# Final_Power_Supply_Design_PCB.net
KiCad netlist of a schematic drawn in EAGLE
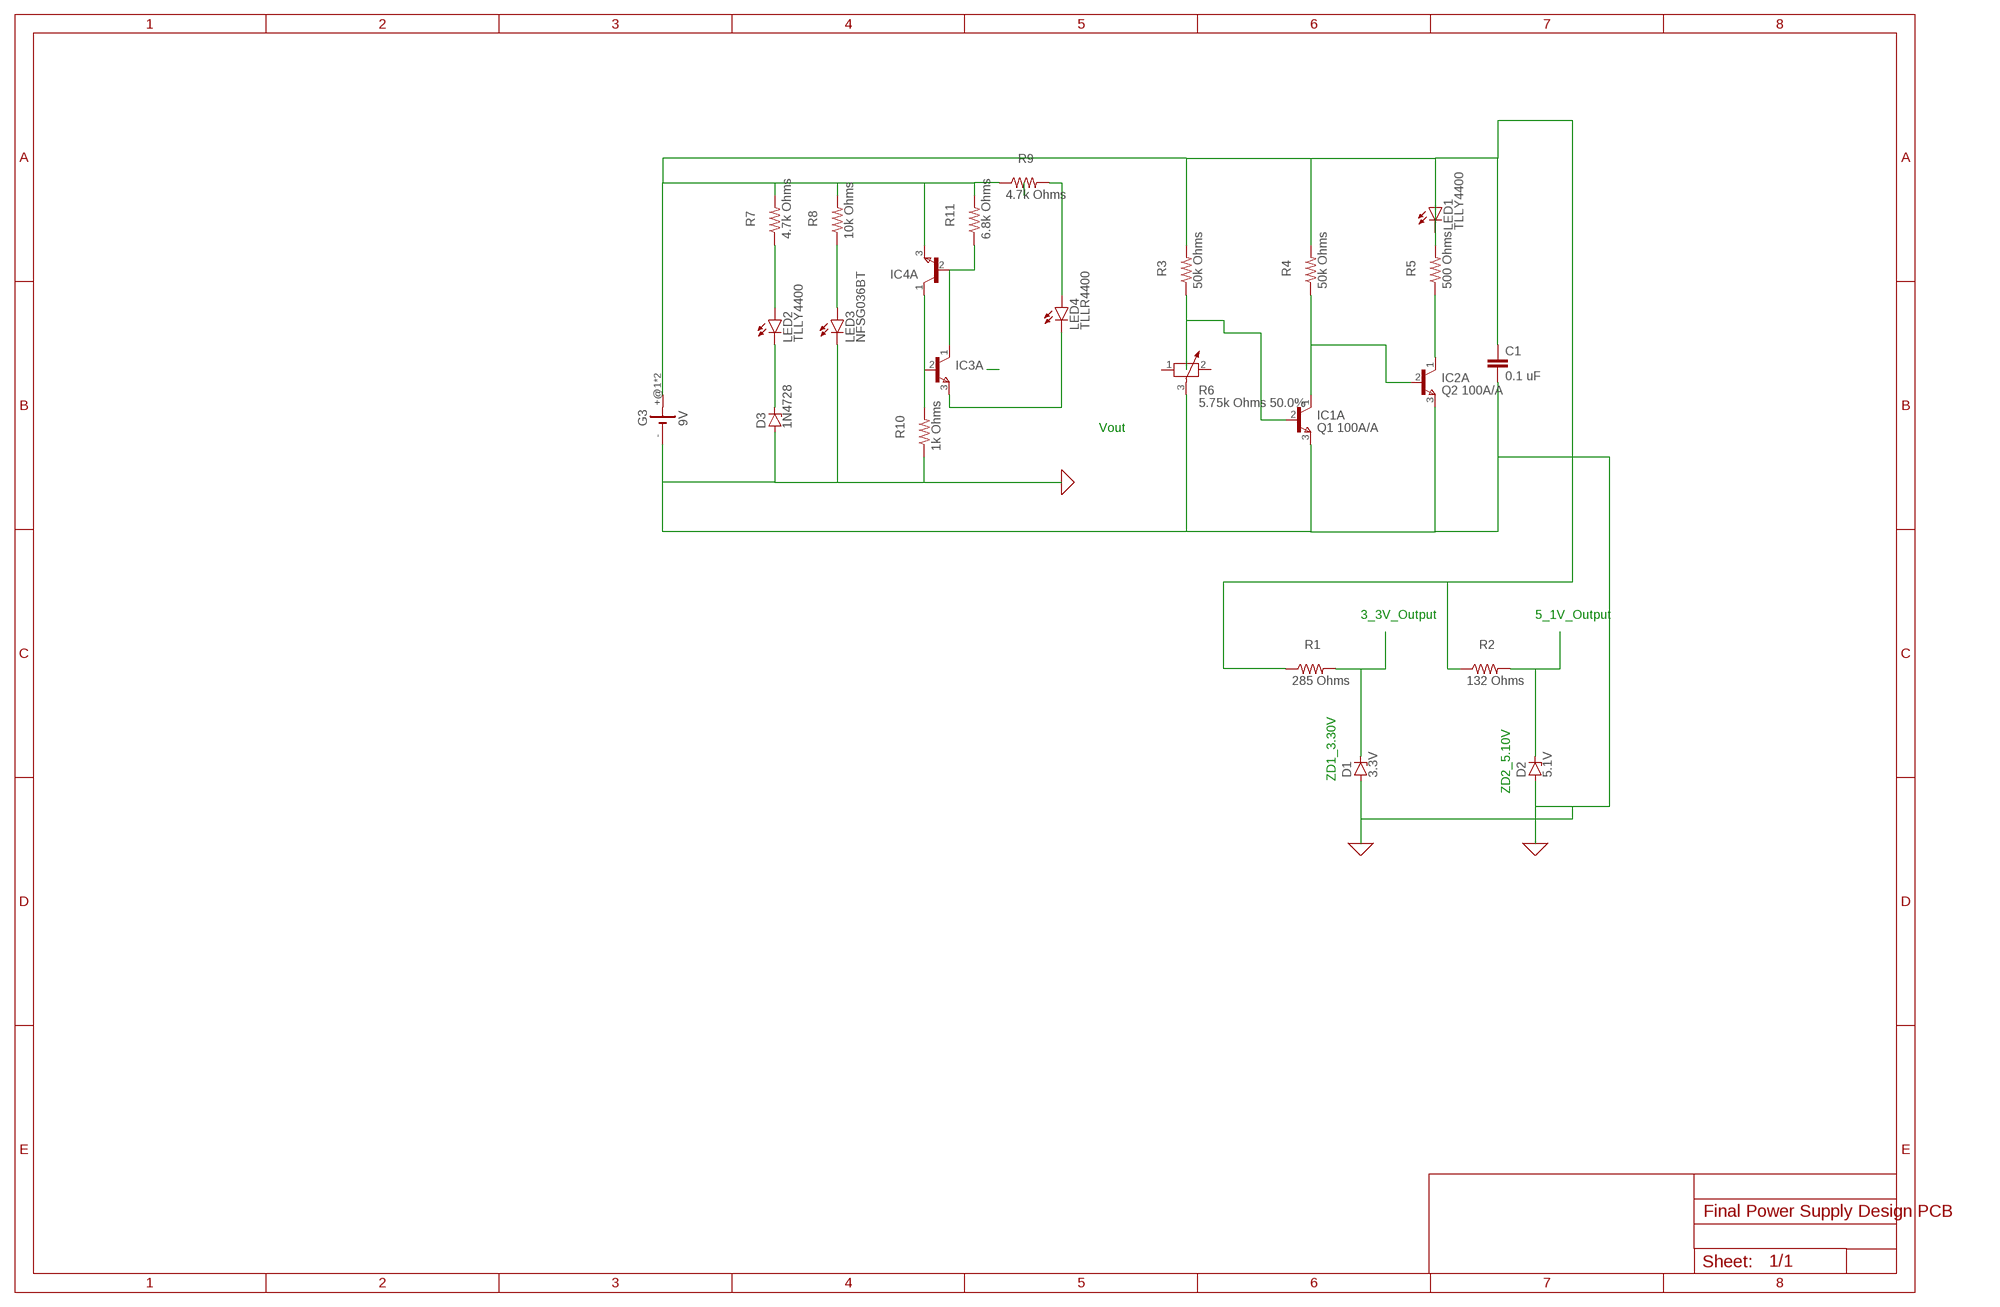
[diagram p0: schematic, sheet 1]

(export (version "E")
  (design (tool "Eeschema 10.0.6"))
  (components
    (comp (ref "C1")
      (value "0.1 uF")
      (footprint "eagle-import:C2.5-4")
      (libsource (lib "eagle-import") (part "C2.5/4"))
    )
    (comp (ref "D1")
      (value "3.3V")
      (footprint "eagle-import:DO41Z10")
      (libsource (lib "eagle-import") (part "1N4728"))
    )
    (comp (ref "D2")
      (value "5.1V")
      (footprint "eagle-import:DO41Z10")
      (libsource (lib "eagle-import") (part "1N4728"))
    )
    (comp (ref "D3")
      (value "1N4728")
      (footprint "eagle-import:DO41Z10")
      (libsource (lib "eagle-import") (part "1N4728"))
    )
    (comp (ref "G3")
      (value "9V")
      (footprint "eagle-import:10MM_SM_COIN_CELL_CLIP")
      (libsource (lib "eagle-import") (part "10MM_SM_COIN_CELL_CLIP"))
    )
    (comp (ref "IC1")
      (value "Q1 100A/A")
      (footprint "eagle-import:TO78")
      (libsource (lib "eagle-import") (part "MAT-01H"))
    )
    (comp (ref "IC2")
      (value "Q2 100A/A")
      (footprint "eagle-import:TO78")
      (libsource (lib "eagle-import") (part "MAT-01H"))
    )
    (comp (ref "IC3")
      (value "MAT-01H")
      (footprint "eagle-import:TO78")
      (libsource (lib "eagle-import") (part "MAT-01H"))
    )
    (comp (ref "IC4")
      (value "MAT-01H")
      (footprint "eagle-import:TO78")
      (libsource (lib "eagle-import") (part "MAT-01H"))
    )
    (comp (ref "LED1")
      (value "TLLY4400")
      (footprint "eagle-import:LED3MM")
      (fields (field (name "MF") "VISHAY SEMICONDUCTOR"))
      (libsource (lib "eagle-import") (part "TLLY4400"))
    )
    (comp (ref "LED2")
      (value "TLLY4400")
      (footprint "eagle-import:LED3MM")
      (fields (field (name "MF") "VISHAY SEMICONDUCTOR"))
      (libsource (lib "eagle-import") (part "TLLY4400"))
    )
    (comp (ref "LED3")
      (value "NFSG036BT")
      (footprint "eagle-import:NFSG036BT")
      (libsource (lib "eagle-import") (part "NFSG036BT"))
    )
    (comp (ref "LED4")
      (value "TLLR4400")
      (footprint "eagle-import:LED3MM")
      (fields (field (name "MF") "VISHAY SEMICONDUCTOR"))
      (libsource (lib "eagle-import") (part "TLLR4400"))
    )
    (comp (ref "R1")
      (value "285 Ohms")
      (footprint "eagle-import:0204V")
      (libsource (lib "eagle-import") (part "R-US_0204/2V"))
    )
    (comp (ref "R2")
      (value "132 Ohms")
      (footprint "eagle-import:0204V")
      (libsource (lib "eagle-import") (part "R-US_0204/2V"))
    )
    (comp (ref "R3")
      (value "50k Ohms")
      (footprint "eagle-import:0204V")
      (libsource (lib "eagle-import") (part "R-US_0204/2V"))
    )
    (comp (ref "R4")
      (value "50k Ohms")
      (footprint "eagle-import:0204V")
      (libsource (lib "eagle-import") (part "R-US_0204/2V"))
    )
    (comp (ref "R5")
      (value "500 Ohms")
      (footprint "eagle-import:0204V")
      (libsource (lib "eagle-import") (part "R-US_0204/2V"))
    )
    (comp (ref "R6")
      (value "5.75k Ohms 50.0%")
      (footprint "eagle-import:PT-10")
      (libsource (lib "eagle-import") (part "POTENTIOMETER_PT-10"))
    )
    (comp (ref "R7")
      (value "4.7k Ohms")
      (footprint "eagle-import:0204V")
      (libsource (lib "eagle-import") (part "R-US_0204/2V"))
    )
    (comp (ref "R8")
      (value "10k Ohms")
      (footprint "eagle-import:0204V")
      (libsource (lib "eagle-import") (part "R-US_0204/2V"))
    )
    (comp (ref "R9")
      (value "4.7k Ohms")
      (footprint "eagle-import:0204V")
      (libsource (lib "eagle-import") (part "R-US_0204/2V"))
    )
    (comp (ref "R10")
      (value "1k Ohms")
      (footprint "eagle-import:0204V")
      (libsource (lib "eagle-import") (part "R-US_0204/2V"))
    )
    (comp (ref "R11")
      (value "6.8k Ohms")
      (footprint "eagle-import:0204V")
      (libsource (lib "eagle-import") (part "R-US_0204/2V"))
    )
  )
  (nets
    (net (code "1") (name "GND") (class "Default")
      (node (ref "C1") (pin "2") (pinfunction "2_2") (pintype "passive"))
      (node (ref "D1") (pin "A") (pinfunction "A_A") (pintype "passive"))
      (node (ref "D2") (pin "A") (pinfunction "A_A") (pintype "passive"))
      (node (ref "D3") (pin "A") (pinfunction "A_A") (pintype "passive"))
      (node (ref "G3") (pin "-") (pinfunction "-_-") (pintype "passive"))
      (node (ref "IC1") (pin "3") (pinfunction "E_3") (pintype "passive"))
      (node (ref "IC2") (pin "3") (pinfunction "E_3") (pintype "passive"))
      (node (ref "LED3") (pin "C") (pinfunction "C_C") (pintype "passive"))
      (node (ref "R10") (pin "1") (pinfunction "1_1") (pintype "passive"))
      (node (ref "R6") (pin "3") (pinfunction "3_3") (pintype "passive"))
    )
    (net (code "2") (name "Net-(D1-PadC)") (class "Default")
      (node (ref "D1") (pin "C") (pinfunction "C_C") (pintype "passive"))
      (node (ref "R1") (pin "2") (pinfunction "2_2") (pintype "passive"))
    )
    (net (code "3") (name "Net-(D2-PadC)") (class "Default")
      (node (ref "D2") (pin "C") (pinfunction "C_C") (pintype "passive"))
      (node (ref "R2") (pin "2") (pinfunction "2_2") (pintype "passive"))
    )
    (net (code "4") (name "Net-(IC1A-B)") (class "Default")
      (node (ref "IC1") (pin "2") (pinfunction "B_2") (pintype "passive"))
      (node (ref "R3") (pin "1") (pinfunction "1_1") (pintype "passive"))
    )
    (net (code "5") (name "Net-(IC1A-C)") (class "Default")
      (node (ref "IC1") (pin "1") (pinfunction "C_1") (pintype "passive"))
      (node (ref "IC2") (pin "2") (pinfunction "B_2") (pintype "passive"))
      (node (ref "R4") (pin "1") (pinfunction "1_1") (pintype "passive"))
    )
    (net (code "6") (name "Net-(IC2A-C)") (class "Default")
      (node (ref "IC2") (pin "1") (pinfunction "C_1") (pintype "passive"))
      (node (ref "R5") (pin "1") (pinfunction "1_1") (pintype "passive"))
    )
    (net (code "7") (name "Net-(IC3A-B)") (class "Default")
      (node (ref "IC3") (pin "2") (pinfunction "B_2") (pintype "passive"))
      (node (ref "IC4") (pin "1") (pinfunction "C_1") (pintype "passive"))
      (node (ref "R10") (pin "2") (pinfunction "2_2") (pintype "passive"))
    )
    (net (code "8") (name "Net-(IC3A-C)") (class "Default")
      (node (ref "IC3") (pin "1") (pinfunction "C_1") (pintype "passive"))
      (node (ref "IC4") (pin "2") (pinfunction "B_2") (pintype "passive"))
      (node (ref "R11") (pin "1") (pinfunction "1_1") (pintype "passive"))
    )
    (net (code "9") (name "Net-(IC3A-E)") (class "Default")
      (node (ref "IC3") (pin "3") (pinfunction "E_3") (pintype "passive"))
      (node (ref "LED4") (pin "K") (pinfunction "C_K") (pintype "passive"))
    )
    (net (code "10") (name "Net-(IC4A-E)") (class "Default")
      (node (ref "C1") (pin "1") (pinfunction "1_1") (pintype "passive"))
      (node (ref "G3") (pin "+@1") (pinfunction "+_+@1") (pintype "passive"))
      (node (ref "G3") (pin "+@2") (pinfunction "+_+@2") (pintype "passive"))
      (node (ref "IC4") (pin "3") (pinfunction "E_3") (pintype "passive"))
      (node (ref "LED1") (pin "A") (pinfunction "A_A") (pintype "passive"))
      (node (ref "LED1") (pin "K") (pinfunction "C_K") (pintype "passive"))
      (node (ref "R1") (pin "1") (pinfunction "1_1") (pintype "passive"))
      (node (ref "R11") (pin "2") (pinfunction "2_2") (pintype "passive"))
      (node (ref "R2") (pin "1") (pinfunction "1_1") (pintype "passive"))
      (node (ref "R3") (pin "2") (pinfunction "2_2") (pintype "passive"))
      (node (ref "R4") (pin "2") (pinfunction "2_2") (pintype "passive"))
      (node (ref "R5") (pin "2") (pinfunction "2_2") (pintype "passive"))
      (node (ref "R7") (pin "2") (pinfunction "2_2") (pintype "passive"))
      (node (ref "R8") (pin "2") (pinfunction "2_2") (pintype "passive"))
      (node (ref "R9") (pin "1") (pinfunction "1_1") (pintype "passive"))
    )
    (net (code "11") (name "Net-(LED2-C)") (class "Default")
      (node (ref "D3") (pin "C") (pinfunction "C_C") (pintype "passive"))
      (node (ref "LED2") (pin "K") (pinfunction "C_K") (pintype "passive"))
    )
    (net (code "12") (name "Net-(LED2-PadA)") (class "Default")
      (node (ref "LED2") (pin "A") (pinfunction "A_A") (pintype "passive"))
      (node (ref "R7") (pin "1") (pinfunction "1_1") (pintype "passive"))
    )
    (net (code "13") (name "Net-(LED3-PadA)") (class "Default")
      (node (ref "LED3") (pin "A") (pinfunction "A_A") (pintype "passive"))
      (node (ref "R8") (pin "1") (pinfunction "1_1") (pintype "passive"))
    )
    (net (code "14") (name "Net-(LED4-PadA)") (class "Default")
      (node (ref "LED4") (pin "A") (pinfunction "A_A") (pintype "passive"))
      (node (ref "R9") (pin "2") (pinfunction "2_2") (pintype "passive"))
    )
    (net (code "15") (name "unconnected-(R6-Pad1)") (class "Default")
      (node (ref "R6") (pin "1") (pinfunction "1_1") (pintype "passive"))
    )
    (net (code "16") (name "unconnected-(R6-Pad2)") (class "Default")
      (node (ref "R6") (pin "2") (pinfunction "2_2") (pintype "passive"))
    )
  )
)
